# Mini_PIC18F-USB_Trainer_SCH.net
KiCad netlist of a schematic drawn in EAGLE
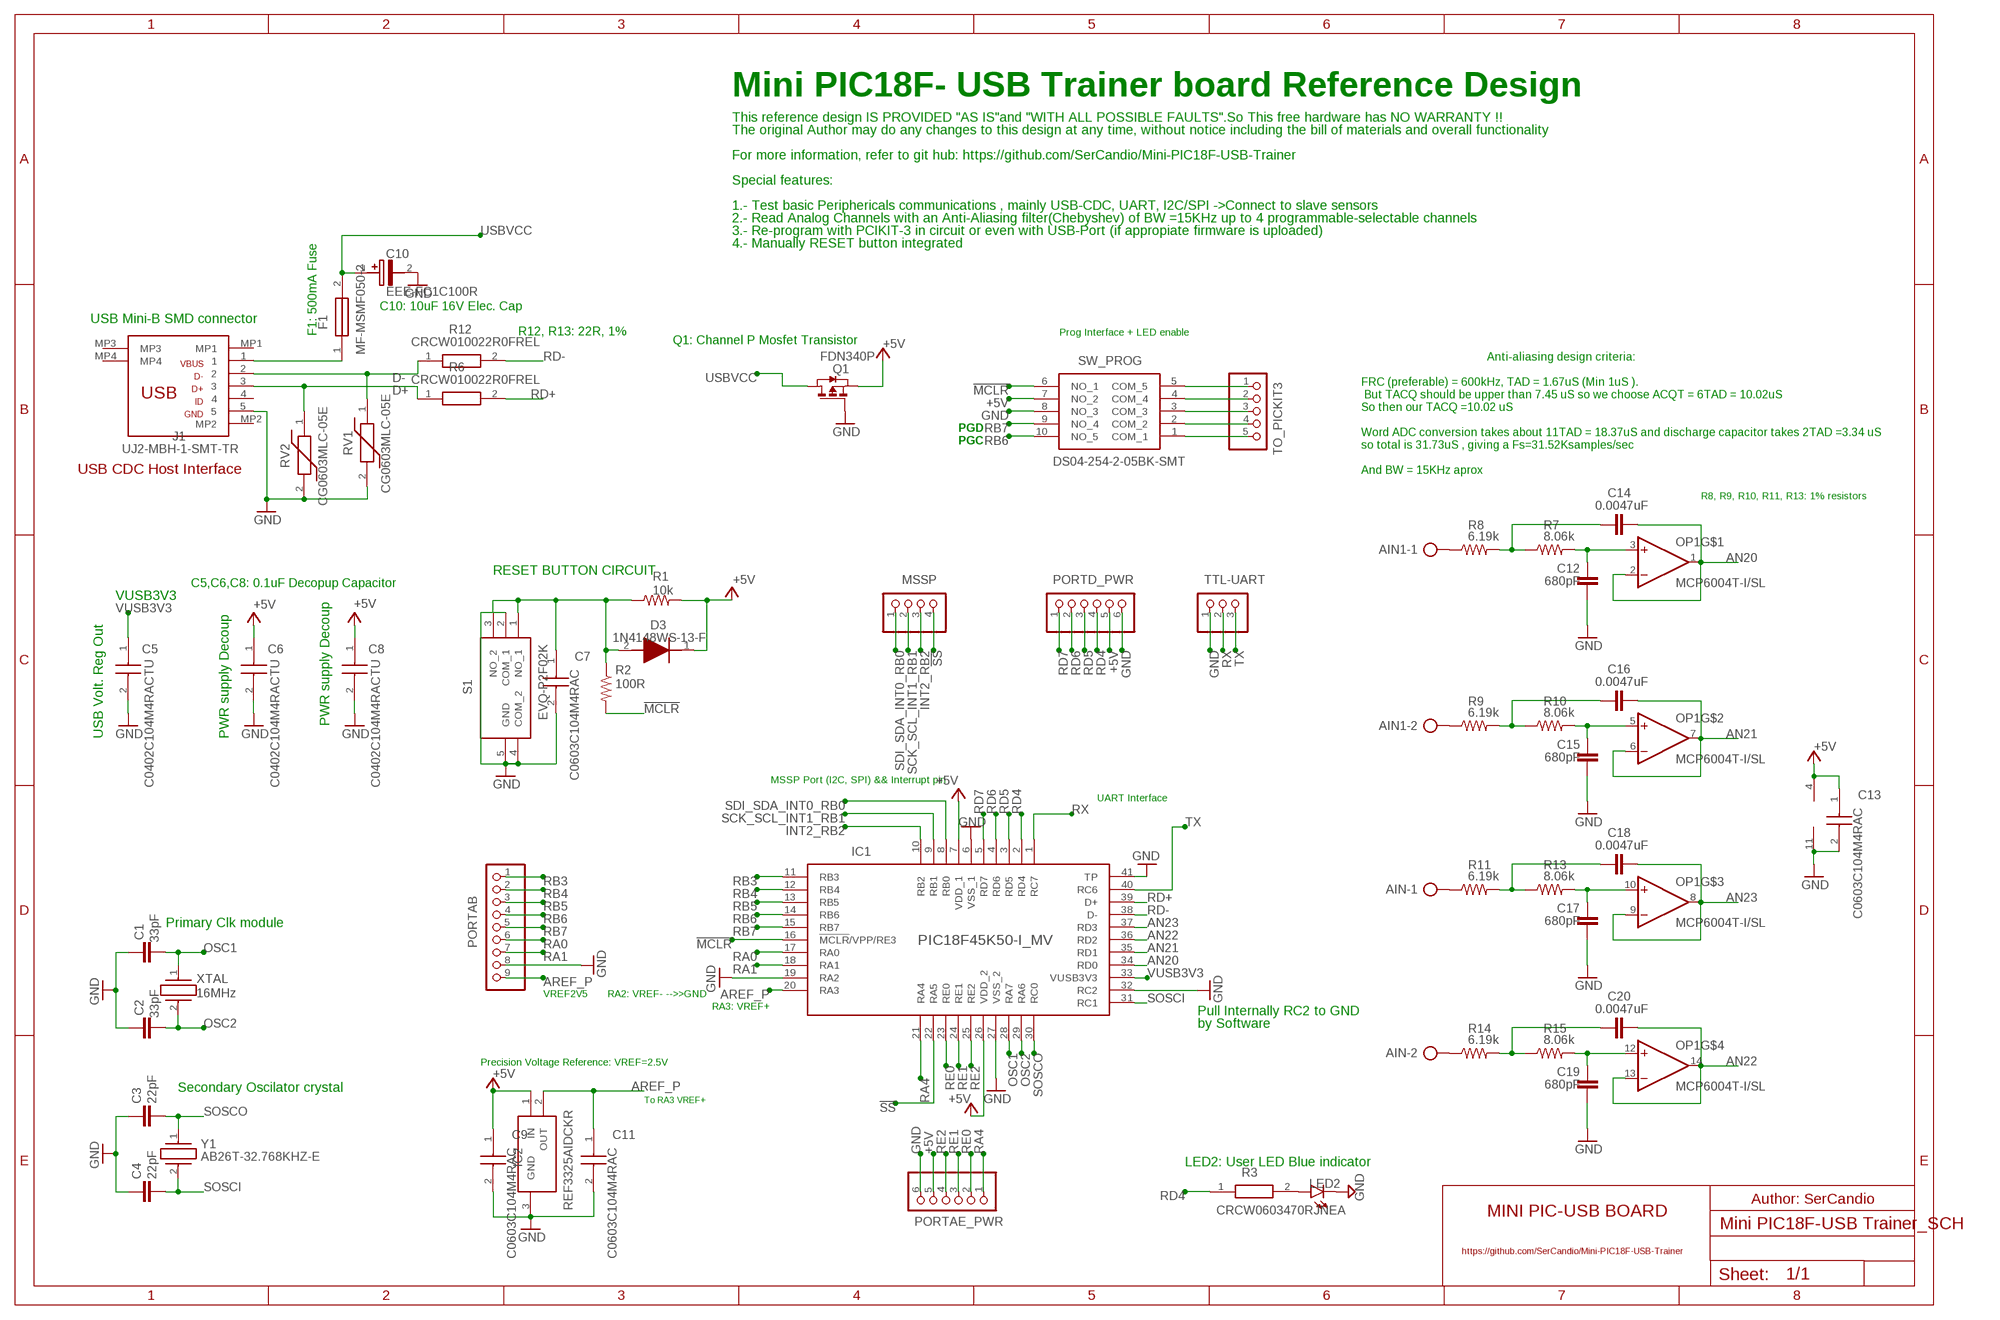
[diagram p0: schematic, sheet 1]

(export (version "E")
  (design (tool "Eeschema 10.0.6"))
  (components
    (comp (ref "AIN")
      (value "AK500/2-H")
      (footprint "eagle-import:AK500_2-H")
      (fields (field (name "LCSC_PART_NUMBER") "C91153") (field (name "MANUFACTURER_PART_NUMBER") "1729128"))
      (libsource (lib "eagle-import") (part "AK500/2-H"))
    )
    (comp (ref "AIN1")
      (value "AK500/2-H")
      (footprint "eagle-import:AK500_2-H")
      (fields (field (name "LCSC_PART_NUMBER") "C91153") (field (name "MANUFACTURER_PART_NUMBER") "1729128"))
      (libsource (lib "eagle-import") (part "AK500/2-H"))
    )
    (comp (ref "C1")
      (value "33pF")
      (footprint "eagle-import:C0603K")
      (description "Capacitores cerámicos de capas múltiples (MLCC) - SMD/SMT WCAP-CSGP 33pF 0603 5% 16V MLCC")
      (fields
        (field (name "MANUFACTURER_PART_NUMBER") "885012006020")
        (field (name "MOUSER_PART_NUMBER") "710-885012006020")
      )
      (libsource (lib "eagle-import") (part "C-EUC0603K"))
    )
    (comp (ref "C2")
      (value "33pF")
      (footprint "eagle-import:C0603K")
      (description "Capacitores cerámicos de capas múltiples (MLCC) - SMD/SMT WCAP-CSGP 33pF 0603 5% 16V MLCC")
      (fields
        (field (name "MANUFACTURER_PART_NUMBER") "885012006020")
        (field (name "MOUSER_PART_NUMBER") "710-885012006020")
      )
      (libsource (lib "eagle-import") (part "C-EUC0603K"))
    )
    (comp (ref "C3")
      (value "22pF")
      (footprint "eagle-import:C0603K")
      (description "Capacitores cerámicos de capas múltiples (MLCC) - SMD/SMT 16V 22pF C0G 0603 5%")
      (fields
        (field (name "MANUFACTURER_PART_NUMBER") "0603YA220JAT2A")
        (field (name "MOUSER_PART_NUMBER") "581-0603YA220JAT2A")
      )
      (libsource (lib "eagle-import") (part "C-EUC0603K"))
    )
    (comp (ref "C4")
      (value "22pF")
      (footprint "eagle-import:C0603K")
      (description "Capacitores cerámicos de capas múltiples (MLCC) - SMD/SMT 16V 22pF C0G 0603 5%")
      (fields
        (field (name "MANUFACTURER_PART_NUMBER") "0603YA220JAT2A")
        (field (name "MOUSER_PART_NUMBER") "581-0603YA220JAT2A")
      )
      (libsource (lib "eagle-import") (part "C-EUC0603K"))
    )
    (comp (ref "C5")
      (value "C0402C104M4RACTU")
      (footprint "eagle-import:C0402C104J4RACTU")
      (fields (field (name "MOUSER_PART_NUMBER") "80-C0402C104M4R"))
      (libsource (lib "eagle-import") (part "C0402C104M4RACTU"))
    )
    (comp (ref "C6")
      (value "C0402C104M4RACTU")
      (footprint "eagle-import:C0402C104J4RACTU")
      (fields (field (name "MOUSER_PART_NUMBER") "80-C0402C104M4R"))
      (libsource (lib "eagle-import") (part "C0402C104M4RACTU"))
    )
    (comp (ref "C7")
      (value "C0603C104M4RAC")
      (footprint "eagle-import:CAPC1608X95N")
      (fields (field (name "MOUSER_PART_NUMBER") "80-C0603C104M4RAC"))
      (libsource (lib "eagle-import") (part "C0603C104M4RAC"))
    )
    (comp (ref "C8")
      (value "C0402C104M4RACTU")
      (footprint "eagle-import:C0402C104J4RACTU")
      (fields (field (name "MOUSER_PART_NUMBER") "80-C0402C104M4R"))
      (libsource (lib "eagle-import") (part "C0402C104M4RACTU"))
    )
    (comp (ref "C9")
      (value "C0603C104M4RAC")
      (footprint "eagle-import:CAPC1608X95N")
      (fields (field (name "MOUSER_PART_NUMBER") "80-C0603C104M4RAC"))
      (libsource (lib "eagle-import") (part "C0603C104M4RAC"))
    )
    (comp (ref "C10")
      (value "EEE-FC1C100R")
      (footprint "eagle-import:EEE1AA220WR")
      (fields (field (name "MOUSER_PART_NUMBER") "667-EEE-FC1C100R"))
      (libsource (lib "eagle-import") (part "EEE-FC1C100R"))
    )
    (comp (ref "C11")
      (value "C0603C104M4RAC")
      (footprint "eagle-import:CAPC1608X95N")
      (fields (field (name "MOUSER_PART_NUMBER") "80-C0603C104M4RAC"))
      (libsource (lib "eagle-import") (part "C0603C104M4RAC"))
    )
    (comp (ref "C12")
      (value "680pF")
      (footprint "eagle-import:C0603K")
      (description "Capacitores cerámicos de capas múltiples (MLCC) - SMD/SMT WCAP-CSGP 680pF 0603 5% 16V MLCC")
      (fields
        (field (name "MANUFACTURER_PART_NUMBER") "885012006028")
        (field (name "MOUSER_PART_NUMBER") "710-885012006028")
      )
      (libsource (lib "eagle-import") (part "C-EUC0603K"))
    )
    (comp (ref "C13")
      (value "C0603C104M4RAC")
      (footprint "eagle-import:CAPC1608X95N")
      (fields (field (name "MOUSER_PART_NUMBER") "80-C0603C104M4RAC"))
      (libsource (lib "eagle-import") (part "C0603C104M4RAC"))
    )
    (comp (ref "C14")
      (value "0.0047uF")
      (footprint "eagle-import:C0603K")
      (description "Capacitores cerámicos de capas múltiples (MLCC) - SMD/SMT 0603 4700pF 16volts X7R 5%")
      (fields
        (field (name "MANUFACTURER_PART_NUMBER") "VJ0603Y472JXJCW1BC")
        (field (name "MOUSER_PART_NUMBER") "77-VJ0603Y472JXJCBC")
      )
      (libsource (lib "eagle-import") (part "C-EUC0603K"))
    )
    (comp (ref "C15")
      (value "680pF")
      (footprint "eagle-import:C0603K")
      (description "Capacitores cerámicos de capas múltiples (MLCC) - SMD/SMT WCAP-CSGP 680pF 0603 5% 16V MLCC")
      (fields
        (field (name "MANUFACTURER_PART_NUMBER") "885012006028")
        (field (name "MOUSER_PART_NUMBER") "710-885012006028")
      )
      (libsource (lib "eagle-import") (part "C-EUC0603K"))
    )
    (comp (ref "C16")
      (value "0.0047uF")
      (footprint "eagle-import:C0603K")
      (description "Capacitores cerámicos de capas múltiples (MLCC) - SMD/SMT 0603 4700pF 16volts X7R 5%")
      (fields
        (field (name "MANUFACTURER_PART_NUMBER") "VJ0603Y472JXJCW1BC")
        (field (name "MOUSER_PART_NUMBER") "77-VJ0603Y472JXJCBC")
      )
      (libsource (lib "eagle-import") (part "C-EUC0603K"))
    )
    (comp (ref "C17")
      (value "680pF")
      (footprint "eagle-import:C0603K")
      (description "Capacitores cerámicos de capas múltiples (MLCC) - SMD/SMT WCAP-CSGP 680pF 0603 5% 16V MLCC")
      (fields
        (field (name "MANUFACTURER_PART_NUMBER") "885012006028")
        (field (name "MOUSER_PART_NUMBER") "710-885012006028")
      )
      (libsource (lib "eagle-import") (part "C-EUC0603K"))
    )
    (comp (ref "C18")
      (value "0.0047uF")
      (footprint "eagle-import:C0603K")
      (description "Capacitores cerámicos de capas múltiples (MLCC) - SMD/SMT 0603 4700pF 16volts X7R 5%")
      (fields
        (field (name "MANUFACTURER_PART_NUMBER") "VJ0603Y472JXJCW1BC")
        (field (name "MOUSER_PART_NUMBER") "77-VJ0603Y472JXJCBC")
      )
      (libsource (lib "eagle-import") (part "C-EUC0603K"))
    )
    (comp (ref "C19")
      (value "680pF")
      (footprint "eagle-import:C0603K")
      (description "Capacitores cerámicos de capas múltiples (MLCC) - SMD/SMT WCAP-CSGP 680pF 0603 5% 16V MLCC")
      (fields
        (field (name "MANUFACTURER_PART_NUMBER") "885012006028")
        (field (name "MOUSER_PART_NUMBER") "710-885012006028")
      )
      (libsource (lib "eagle-import") (part "C-EUC0603K"))
    )
    (comp (ref "C20")
      (value "0.0047uF")
      (footprint "eagle-import:C0603K")
      (description "Capacitores cerámicos de capas múltiples (MLCC) - SMD/SMT 0603 4700pF 16volts X7R 5%")
      (fields
        (field (name "MANUFACTURER_PART_NUMBER") "VJ0603Y472JXJCW1BC")
        (field (name "MOUSER_PART_NUMBER") "77-VJ0603Y472JXJCBC")
      )
      (libsource (lib "eagle-import") (part "C-EUC0603K"))
    )
    (comp (ref "D3")
      (value "1N4148WS-13-F")
      (footprint "eagle-import:SOD2513X120N")
      (fields (field (name "MOUSER_PART_NUMBER") "621-1N4148WS-13-F"))
      (libsource (lib "eagle-import") (part "1N4148WS-13-F"))
    )
    (comp (ref "F1")
      (value "MF-MSMF050-2")
      (footprint "eagle-import:FUSC4632X85N")
      (fields (field (name "MOUSER_PART_NUMBER") "652-MF-MSMF050-2"))
      (libsource (lib "eagle-import") (part "MF-MSMF050-2"))
    )
    (comp (ref "IC1")
      (value "PIC18F45K50-I_MV")
      (footprint "eagle-import:QFN40P500X500X55-41N")
      (fields
        (field (name "MANUFACTURER_PART_NUMBER") "PIC18F45K50-I/MV")
        (field (name "MOUSER_PART_NUMBER") "579-PIC18F45K50-I/MV")
      )
      (libsource (lib "eagle-import") (part "PIC18F45K50-I_MV"))
    )
    (comp (ref "IC2")
      (value "REF3325AIDCKR")
      (footprint "eagle-import:SOT65P210X110-3N")
      (fields (field (name "MOUSER_PART_NUMBER") "595-REF3325AIDCKR"))
      (libsource (lib "eagle-import") (part "REF3325AIDCKR"))
    )
    (comp (ref "J1")
      (value "UJ2-MBH-1-SMT-TR")
      (footprint "eagle-import:UJ2MBH1SMTTR")
      (fields (field (name "MOUSER_PART_NUMBER") "490-UJ2-MBH-1-SMT"))
      (libsource (lib "eagle-import") (part "UJ2-MBH-1-SMT-TR"))
    )
    (comp (ref "LED2")
      (value "LEDCHIP-LED0805")
      (footprint "eagle-import:CHIP-LED0805")
      (description "LED estándar - SMD (montaje superficial) WL-SMCW SMDMono TpVw Waterclr 0805 Blue")
      (fields
        (field (name "MANUFACTURER_PART_NUMBER") "150080BS75000")
        (field (name "MOUSER_PART_NUMBER") "710-150080BS75000")
      )
      (libsource (lib "eagle-import") (part "LEDCHIP-LED0805"))
    )
    (comp (ref "MSSP")
      (value "PINHD-1X4")
      (footprint "eagle-import:1X04")
      (libsource (lib "eagle-import") (part "PINHD-1X4"))
    )
    (comp (ref "OP1")
      (value "MCP6004T-I/SL")
      (footprint "eagle-import:SOIC127P600X175-14M")
      (fields
        (field (name "LCSC_PART_NUMBER") "C7378")
        (field (name "MANUFACTURER_PART_NUMBER") " MCP6004T-I/SL")
        (field (name "MOUSER_PART_NUMBER") "579-MCP6004T-I/SL")
      )
      (libsource (lib "eagle-import") (part "MCP6004T-I/SL"))
    )
    (comp (ref "PORTAB")
      (value "PINHD-1X9")
      (footprint "eagle-import:1X09")
      (libsource (lib "eagle-import") (part "PINHD-1X9"))
    )
    (comp (ref "PORTAE_PWR")
      (value "PINHD-1X6")
      (footprint "eagle-import:1X06")
      (libsource (lib "eagle-import") (part "PINHD-1X6"))
    )
    (comp (ref "PORTD_PWR")
      (value "PINHD-1X6")
      (footprint "eagle-import:1X06")
      (libsource (lib "eagle-import") (part "PINHD-1X6"))
    )
    (comp (ref "Q1")
      (value "FDN340P")
      (footprint "eagle-import:SOT95P237X112-3N")
      (fields (field (name "MOUSER_PART_NUMBER") "512-FDN340P"))
      (libsource (lib "eagle-import") (part "FDN340P"))
    )
    (comp (ref "R1")
      (value "10k")
      (footprint "eagle-import:R0402")
      (description "Resistores de película gruesa - SMD 10K OHM 5%")
      (fields
        (field (name "MANUFACTURER_PART_NUMBER") "CR0402-JW-103GLF")
        (field (name "MOUSER_PART_NUMBER") "652-CR0402-JW-103GLF")
      )
      (libsource (lib "eagle-import") (part "R-US_R0402"))
    )
    (comp (ref "R2")
      (value "100R")
      (footprint "eagle-import:R0402")
      (description "Resistores de película gruesa - SMD 100 OHM 5%")
      (fields
        (field (name "MANUFACTURER_PART_NUMBER") "CR0402-JW-101GLF")
        (field (name "MOUSER_PART_NUMBER") "652-CR0402JW-101GLF")
      )
      (libsource (lib "eagle-import") (part "R-US_R0402"))
    )
    (comp (ref "R3")
      (value "CRCW0603470RJNEA")
      (footprint "eagle-import:RESC1608X50N")
      (fields (field (name "MOUSER_PART_NUMBER") "71-CRCW0603J-470-E3"))
      (libsource (lib "eagle-import") (part "CRCW0603470RJNEA"))
    )
    (comp (ref "R6")
      (value "CRCW010022R0FREL")
      (footprint "eagle-import:RESC0402X15N")
      (fields (field (name "MOUSER_PART_NUMBER") "71-CRCW010022R0FREL"))
      (libsource (lib "eagle-import") (part "CRCW010022R0FREL"))
    )
    (comp (ref "R7")
      (value "8.06k")
      (footprint "eagle-import:R0603")
      (description "Resistores de película gruesa - SMD 8.06K ohm 1%")
      (fields
        (field (name "MANUFACTURER_PART_NUMBER") "CR0603-FX-8061ELF")
        (field (name "MOUSER_PART_NUMBER") "652-CR0603FX-8061ELF")
      )
      (libsource (lib "eagle-import") (part "R-US_R0603"))
    )
    (comp (ref "R8")
      (value "6.19k")
      (footprint "eagle-import:R0603")
      (description "Resistores de película gruesa - SMD 6.19K ohm 1%")
      (fields
        (field (name "MANUFACTURER_PART_NUMBER") "CR0603-FX-6191ELF")
        (field (name "MOUSER_PART_NUMBER") "652-CR0603FX-6191ELF")
      )
      (libsource (lib "eagle-import") (part "R-US_R0603"))
    )
    (comp (ref "R9")
      (value "6.19k")
      (footprint "eagle-import:R0603")
      (description "Resistores de película gruesa - SMD 6.19K ohm 1%")
      (fields
        (field (name "MANUFACTURER_PART_NUMBER") "CR0603-FX-6191ELF")
        (field (name "MOUSER_PART_NUMBER") "652-CR0603FX-6191ELF")
      )
      (libsource (lib "eagle-import") (part "R-US_R0603"))
    )
    (comp (ref "R10")
      (value "8.06k")
      (footprint "eagle-import:R0603")
      (description "Resistores de película gruesa - SMD 8.06K ohm 1%")
      (fields
        (field (name "MANUFACTURER_PART_NUMBER") "CR0603-FX-8061ELF")
        (field (name "MOUSER_PART_NUMBER") "652-CR0603FX-8061ELF")
      )
      (libsource (lib "eagle-import") (part "R-US_R0603"))
    )
    (comp (ref "R11")
      (value "6.19k")
      (footprint "eagle-import:R0603")
      (description "Resistores de película gruesa - SMD 6.19K ohm 1%")
      (fields
        (field (name "MANUFACTURER_PART_NUMBER") "CR0603-FX-6191ELF")
        (field (name "MOUSER_PART_NUMBER") "652-CR0603FX-6191ELF")
      )
      (libsource (lib "eagle-import") (part "R-US_R0603"))
    )
    (comp (ref "R12")
      (value "CRCW010022R0FREL")
      (footprint "eagle-import:RESC0402X15N")
      (fields (field (name "MOUSER_PART_NUMBER") "71-CRCW010022R0FREL"))
      (libsource (lib "eagle-import") (part "CRCW010022R0FREL"))
    )
    (comp (ref "R13")
      (value "8.06k")
      (footprint "eagle-import:R0603")
      (description "Resistores de película gruesa - SMD 8.06K ohm 1%")
      (fields
        (field (name "MANUFACTURER_PART_NUMBER") "CR0603-FX-8061ELF")
        (field (name "MOUSER_PART_NUMBER") "652-CR0603FX-8061ELF")
      )
      (libsource (lib "eagle-import") (part "R-US_R0603"))
    )
    (comp (ref "R14")
      (value "6.19k")
      (footprint "eagle-import:R0603")
      (description "Resistores de película gruesa - SMD 6.19K ohm 1%")
      (fields
        (field (name "MANUFACTURER_PART_NUMBER") "CR0603-FX-6191ELF")
        (field (name "MOUSER_PART_NUMBER") "652-CR0603FX-6191ELF")
      )
      (libsource (lib "eagle-import") (part "R-US_R0603"))
    )
    (comp (ref "R15")
      (value "8.06k")
      (footprint "eagle-import:R0603")
      (description "Resistores de película gruesa - SMD 8.06K ohm 1%")
      (fields
        (field (name "MANUFACTURER_PART_NUMBER") "CR0603-FX-8061ELF")
        (field (name "MOUSER_PART_NUMBER") "652-CR0603FX-8061ELF")
      )
      (libsource (lib "eagle-import") (part "R-US_R0603"))
    )
    (comp (ref "RV1")
      (value "CG0603MLC-05E")
      (footprint "eagle-import:VARC1608X55N")
      (fields (field (name "MOUSER_PART_NUMBER") "652-CG0603MLC-05E"))
      (libsource (lib "eagle-import") (part "CG0603MLC-05E"))
    )
    (comp (ref "RV2")
      (value "CG0603MLC-05E")
      (footprint "eagle-import:VARC1608X55N")
      (fields (field (name "MOUSER_PART_NUMBER") "652-CG0603MLC-05E"))
      (libsource (lib "eagle-import") (part "CG0603MLC-05E"))
    )
    (comp (ref "S1")
      (value "EVQ-P2F02K")
      (footprint "eagle-import:EVQP2V02W")
      (fields (field (name "MOUSER_PART_NUMBER") "667-EVQ-P2F02K"))
      (libsource (lib "eagle-import") (part "EVQ-P2F02K"))
    )
    (comp (ref "SW_PROG")
      (value "DS04-254-2-05BK-SMT")
      (footprint "eagle-import:DS04254205BKSMT")
      (fields (field (name "MOUSER_PART_NUMBER") "490-DS04254205BK-SMT"))
      (libsource (lib "eagle-import") (part "DS04-254-2-05BK-SMT"))
    )
    (comp (ref "TO_PICKIT3")
      (value "PINHD-1X5/90")
      (footprint "eagle-import:1X05_90")
      (libsource (lib "eagle-import") (part "PINHD-1X5/90"))
    )
    (comp (ref "TTL-UART")
      (value "PINHD-1X3/90")
      (footprint "eagle-import:1X03_90")
      (libsource (lib "eagle-import") (part "PINHD-1X3/90"))
    )
    (comp (ref "XTAL")
      (value "16MHz")
      (footprint "eagle-import:LFXTAL020423CUTT")
      (fields
        (field (name "MANUFACTURER_PART_NUMBER") "LFXTAL003237REEL")
        (field (name "MOUSER_PART_NUMBER") "449-LFXTAL003237REEL")
      )
      (libsource (lib "eagle-import") (part "LFXTAL003237REEL"))
    )
    (comp (ref "Y1")
      (value "AB26T-32.768KHZ-E")
      (footprint "eagle-import:AB26T32768KHZE")
      (fields (field (name "MOUSER_PART_NUMBER") "815-AB26T32.768KHZE"))
      (libsource (lib "eagle-import") (part "AB26T-32.768KHZ-E"))
    )
  )
  (nets
    (net (code "1") (name "+5V") (class "Default")
      (node (ref "C13") (pin "1") (pinfunction "1_1") (pintype "bidirectional"))
      (node (ref "C6") (pin "1") (pinfunction "1_1") (pintype "bidirectional"))
      (node (ref "C8") (pin "1") (pinfunction "1_1") (pintype "bidirectional"))
      (node (ref "C9") (pin "1") (pinfunction "1_1") (pintype "bidirectional"))
      (node (ref "D3") (pin "1") (pinfunction "K_1") (pintype "bidirectional"))
      (node (ref "IC1") (pin "26") (pinfunction "VDD_2_26") (pintype "bidirectional"))
      (node (ref "IC1") (pin "7") (pinfunction "VDD_1_7") (pintype "bidirectional"))
      (node (ref "IC2") (pin "1") (pinfunction "IN_1") (pintype "bidirectional"))
      (node (ref "OP1") (pin "4") (pinfunction "V+_4") (pintype "power_in"))
      (node (ref "PORTAE_PWR") (pin "5") (pinfunction "5_5") (pintype "passive"))
      (node (ref "PORTD_PWR") (pin "5") (pinfunction "5_5") (pintype "passive"))
      (node (ref "Q1") (pin "2") (pinfunction "S_2") (pintype "passive"))
      (node (ref "R1") (pin "2") (pinfunction "2_2") (pintype "passive"))
      (node (ref "SW_PROG") (pin "7") (pinfunction "NO_2_7") (pintype "bidirectional"))
    )
    (net (code "2") (name "/AN20") (class "Default")
      (node (ref "C14") (pin "2") (pinfunction "2_2") (pintype "passive"))
      (node (ref "IC1") (pin "34") (pinfunction "RD0_34") (pintype "bidirectional"))
      (node (ref "OP1") (pin "1") (pinfunction "OUT_1") (pintype "output"))
      (node (ref "OP1") (pin "2") (pinfunction "-IN_2") (pintype "input"))
    )
    (net (code "3") (name "/AN21") (class "Default")
      (node (ref "C16") (pin "2") (pinfunction "2_2") (pintype "passive"))
      (node (ref "IC1") (pin "35") (pinfunction "RD1_35") (pintype "bidirectional"))
      (node (ref "OP1") (pin "6") (pinfunction "-IN_6") (pintype "input"))
      (node (ref "OP1") (pin "7") (pinfunction "OUT_7") (pintype "output"))
    )
    (net (code "4") (name "/AN22") (class "Default")
      (node (ref "C20") (pin "2") (pinfunction "2_2") (pintype "passive"))
      (node (ref "IC1") (pin "36") (pinfunction "RD2_36") (pintype "bidirectional"))
      (node (ref "OP1") (pin "13") (pinfunction "-IN_13") (pintype "input"))
      (node (ref "OP1") (pin "14") (pinfunction "OUT_14") (pintype "output"))
    )
    (net (code "5") (name "/AN23") (class "Default")
      (node (ref "C18") (pin "2") (pinfunction "2_2") (pintype "passive"))
      (node (ref "IC1") (pin "37") (pinfunction "RD3_37") (pintype "bidirectional"))
      (node (ref "OP1") (pin "8") (pinfunction "OUT_8") (pintype "output"))
      (node (ref "OP1") (pin "9") (pinfunction "-IN_9") (pintype "input"))
    )
    (net (code "6") (name "/AREF_P") (class "Default")
      (node (ref "C11") (pin "1") (pinfunction "1_1") (pintype "bidirectional"))
      (node (ref "IC1") (pin "20") (pinfunction "RA3_20") (pintype "bidirectional"))
      (node (ref "IC2") (pin "2") (pinfunction "OUT_2") (pintype "bidirectional"))
      (node (ref "PORTAB") (pin "9") (pinfunction "9_9") (pintype "passive"))
    )
    (net (code "7") (name "/D+") (class "Default")
      (node (ref "J1") (pin "3") (pinfunction "3_3") (pintype "bidirectional"))
      (node (ref "R6") (pin "1") (pinfunction "1_1") (pintype "bidirectional"))
      (node (ref "RV2") (pin "1") (pinfunction "1_1") (pintype "bidirectional"))
    )
    (net (code "8") (name "/D-") (class "Default")
      (node (ref "J1") (pin "2") (pinfunction "2_2") (pintype "bidirectional"))
      (node (ref "R12") (pin "1") (pinfunction "1_1") (pintype "bidirectional"))
      (node (ref "RV1") (pin "1") (pinfunction "1_1") (pintype "bidirectional"))
    )
    (net (code "9") (name "/INT2_RB2") (class "Default")
      (node (ref "IC1") (pin "10") (pinfunction "RB2_10") (pintype "bidirectional"))
      (node (ref "MSSP") (pin "3") (pinfunction "3_3") (pintype "passive"))
    )
    (net (code "10") (name "/OSC1") (class "Default")
      (node (ref "C1") (pin "2") (pinfunction "2_2") (pintype "passive"))
      (node (ref "IC1") (pin "28") (pinfunction "RA7_28") (pintype "bidirectional"))
      (node (ref "XTAL") (pin "1") (pinfunction "1_1") (pintype "bidirectional"))
    )
    (net (code "11") (name "/OSC2") (class "Default")
      (node (ref "C2") (pin "2") (pinfunction "2_2") (pintype "passive"))
      (node (ref "IC1") (pin "29") (pinfunction "RA6_29") (pintype "bidirectional"))
      (node (ref "XTAL") (pin "2") (pinfunction "2_2") (pintype "bidirectional"))
    )
    (net (code "12") (name "/RA0") (class "Default")
      (node (ref "IC1") (pin "17") (pinfunction "RA0_17") (pintype "bidirectional"))
      (node (ref "PORTAB") (pin "6") (pinfunction "6_6") (pintype "passive"))
    )
    (net (code "13") (name "/RA1") (class "Default")
      (node (ref "IC1") (pin "18") (pinfunction "RA1_18") (pintype "bidirectional"))
      (node (ref "PORTAB") (pin "7") (pinfunction "7_7") (pintype "passive"))
    )
    (net (code "14") (name "/RA4") (class "Default")
      (node (ref "IC1") (pin "21") (pinfunction "RA4_21") (pintype "bidirectional"))
      (node (ref "PORTAE_PWR") (pin "1") (pinfunction "1_1") (pintype "passive"))
    )
    (net (code "15") (name "/RB3") (class "Default")
      (node (ref "IC1") (pin "11") (pinfunction "RB3_11") (pintype "bidirectional"))
      (node (ref "PORTAB") (pin "1") (pinfunction "1_1") (pintype "passive"))
    )
    (net (code "16") (name "/RB4") (class "Default")
      (node (ref "IC1") (pin "12") (pinfunction "RB4_12") (pintype "bidirectional"))
      (node (ref "PORTAB") (pin "2") (pinfunction "2_2") (pintype "passive"))
    )
    (net (code "17") (name "/RB5") (class "Default")
      (node (ref "IC1") (pin "13") (pinfunction "RB5_13") (pintype "bidirectional"))
      (node (ref "PORTAB") (pin "3") (pinfunction "3_3") (pintype "passive"))
    )
    (net (code "18") (name "/RB6") (class "Default")
      (node (ref "IC1") (pin "14") (pinfunction "RB6_14") (pintype "bidirectional"))
      (node (ref "PORTAB") (pin "4") (pinfunction "4_4") (pintype "passive"))
      (node (ref "SW_PROG") (pin "10") (pinfunction "NO_5_10") (pintype "bidirectional"))
    )
    (net (code "19") (name "/RB7") (class "Default")
      (node (ref "IC1") (pin "15") (pinfunction "RB7_15") (pintype "bidirectional"))
      (node (ref "PORTAB") (pin "5") (pinfunction "5_5") (pintype "passive"))
      (node (ref "SW_PROG") (pin "9") (pinfunction "NO_4_9") (pintype "bidirectional"))
    )
    (net (code "20") (name "/RD+") (class "Default")
      (node (ref "IC1") (pin "39") (pinfunction "D+_39") (pintype "bidirectional"))
      (node (ref "R6") (pin "2") (pinfunction "2_2") (pintype "bidirectional"))
    )
    (net (code "21") (name "/RD-") (class "Default")
      (node (ref "IC1") (pin "38") (pinfunction "D-_38") (pintype "bidirectional"))
      (node (ref "R12") (pin "2") (pinfunction "2_2") (pintype "bidirectional"))
    )
    (net (code "22") (name "/RD4") (class "Default")
      (node (ref "IC1") (pin "2") (pinfunction "RD4_2") (pintype "bidirectional"))
      (node (ref "PORTD_PWR") (pin "4") (pinfunction "4_4") (pintype "passive"))
      (node (ref "R3") (pin "1") (pinfunction "1_1") (pintype "bidirectional"))
    )
    (net (code "23") (name "/RD5") (class "Default")
      (node (ref "IC1") (pin "3") (pinfunction "RD5_3") (pintype "bidirectional"))
      (node (ref "PORTD_PWR") (pin "3") (pinfunction "3_3") (pintype "passive"))
    )
    (net (code "24") (name "/RD6") (class "Default")
      (node (ref "IC1") (pin "4") (pinfunction "RD6_4") (pintype "bidirectional"))
      (node (ref "PORTD_PWR") (pin "2") (pinfunction "2_2") (pintype "passive"))
    )
    (net (code "25") (name "/RD7") (class "Default")
      (node (ref "IC1") (pin "5") (pinfunction "RD7_5") (pintype "bidirectional"))
      (node (ref "PORTD_PWR") (pin "1") (pinfunction "1_1") (pintype "passive"))
    )
    (net (code "26") (name "/RE0") (class "Default")
      (node (ref "IC1") (pin "23") (pinfunction "RE0_23") (pintype "bidirectional"))
      (node (ref "PORTAE_PWR") (pin "2") (pinfunction "2_2") (pintype "passive"))
    )
    (net (code "27") (name "/RE1") (class "Default")
      (node (ref "IC1") (pin "24") (pinfunction "RE1_24") (pintype "bidirectional"))
      (node (ref "PORTAE_PWR") (pin "3") (pinfunction "3_3") (pintype "passive"))
    )
    (net (code "28") (name "/RE2") (class "Default")
      (node (ref "IC1") (pin "25") (pinfunction "RE2_25") (pintype "bidirectional"))
      (node (ref "PORTAE_PWR") (pin "4") (pinfunction "4_4") (pintype "passive"))
    )
    (net (code "29") (name "/RX") (class "Default")
      (node (ref "IC1") (pin "1") (pinfunction "RC7_1") (pintype "bidirectional"))
      (node (ref "TTL-UART") (pin "2") (pinfunction "2_2") (pintype "passive"))
    )
    (net (code "30") (name "/SCK_SCL_INT1_RB1") (class "Default")
      (node (ref "IC1") (pin "9") (pinfunction "RB1_9") (pintype "bidirectional"))
      (node (ref "MSSP") (pin "2") (pinfunction "2_2") (pintype "passive"))
    )
    (net (code "31") (name "/SDI_SDA_INT0_RB0") (class "Default")
      (node (ref "IC1") (pin "8") (pinfunction "RB0_8") (pintype "bidirectional"))
      (node (ref "MSSP") (pin "1") (pinfunction "1_1") (pintype "passive"))
    )
    (net (code "32") (name "/SOSCI") (class "Default")
      (node (ref "C4") (pin "2") (pinfunction "2_2") (pintype "passive"))
      (node (ref "IC1") (pin "31") (pinfunction "RC1_31") (pintype "bidirectional"))
      (node (ref "Y1") (pin "2") (pinfunction "2_2") (pintype "bidirectional"))
    )
    (net (code "33") (name "/SOSCO") (class "Default")
      (node (ref "C3") (pin "2") (pinfunction "2_2") (pintype "passive"))
      (node (ref "IC1") (pin "30") (pinfunction "RC0_30") (pintype "bidirectional"))
      (node (ref "Y1") (pin "1") (pinfunction "1_1") (pintype "bidirectional"))
    )
    (net (code "34") (name "/TX") (class "Default")
      (node (ref "IC1") (pin "40") (pinfunction "RC6_40") (pintype "bidirectional"))
      (node (ref "TTL-UART") (pin "3") (pinfunction "3_3") (pintype "passive"))
    )
    (net (code "35") (name "/USBVCC") (class "Default")
      (node (ref "C10") (pin "1") (pinfunction "+_1") (pintype "bidirectional"))
      (node (ref "F1") (pin "2") (pinfunction "2_2") (pintype "bidirectional"))
      (node (ref "Q1") (pin "3") (pinfunction "D_3") (pintype "passive"))
    )
    (net (code "36") (name "/VUSB3V3") (class "Default")
      (node (ref "C5") (pin "1") (pinfunction "1_1") (pintype "bidirectional"))
      (node (ref "IC1") (pin "33") (pinfunction "VUSB3V3_33") (pintype "bidirectional"))
    )
    (net (code "37") (name "/~{MCLR}") (class "Default")
      (node (ref "IC1") (pin "16") (pinfunction "~{MCLR}/VPP/RE3_16") (pintype "bidirectional"))
      (node (ref "R2") (pin "2") (pinfunction "2_2") (pintype "passive"))
      (node (ref "SW_PROG") (pin "6") (pinfunction "NO_1_6") (pintype "bidirectional"))
    )
    (net (code "38") (name "/~{SS}") (class "Default")
      (node (ref "IC1") (pin "22") (pinfunction "RA5_22") (pintype "bidirectional"))
      (node (ref "MSSP") (pin "4") (pinfunction "4_4") (pintype "passive"))
    )
    (net (code "39") (name "GND") (class "Default")
      (node (ref "C1") (pin "1") (pinfunction "1_1") (pintype "passive"))
      (node (ref "C10") (pin "2") (pinfunction "-_2") (pintype "bidirectional"))
      (node (ref "C11") (pin "2") (pinfunction "2_2") (pintype "bidirectional"))
      (node (ref "C12") (pin "2") (pinfunction "2_2") (pintype "passive"))
      (node (ref "C13") (pin "2") (pinfunction "2_2") (pintype "bidirectional"))
      (node (ref "C15") (pin "2") (pinfunction "2_2") (pintype "passive"))
      (node (ref "C17") (pin "2") (pinfunction "2_2") (pintype "passive"))
      (node (ref "C19") (pin "2") (pinfunction "2_2") (pintype "passive"))
      (node (ref "C2") (pin "1") (pinfunction "1_1") (pintype "passive"))
      (node (ref "C3") (pin "1") (pinfunction "1_1") (pintype "passive"))
      (node (ref "C4") (pin "1") (pinfunction "1_1") (pintype "passive"))
      (node (ref "C5") (pin "2") (pinfunction "2_2") (pintype "bidirectional"))
      (node (ref "C6") (pin "2") (pinfunction "2_2") (pintype "bidirectional"))
      (node (ref "C7") (pin "2") (pinfunction "2_2") (pintype "bidirectional"))
      (node (ref "C8") (pin "2") (pinfunction "2_2") (pintype "bidirectional"))
      (node (ref "C9") (pin "2") (pinfunction "2_2") (pintype "bidirectional"))
      (node (ref "IC1") (pin "19") (pinfunction "RA2_19") (pintype "bidirectional"))
      (node (ref "IC1") (pin "27") (pinfunction "VSS_2_27") (pintype "bidirectional"))
      (node (ref "IC1") (pin "32") (pinfunction "RC2_32") (pintype "bidirectional"))
      (node (ref "IC1") (pin "41") (pinfunction "TP_41") (pintype "bidirectional"))
      (node (ref "IC1") (pin "6") (pinfunction "VSS_1_6") (pintype "bidirectional"))
      (node (ref "IC2") (pin "3") (pinfunction "GND_3") (pintype "bidirectional"))
      (node (ref "J1") (pin "5") (pinfunction "5_5") (pintype "bidirectional"))
      (node (ref "LED2") (pin "C") (pinfunction "C_C") (pintype "passive"))
      (node (ref "OP1") (pin "11") (pinfunction "V-_11") (pintype "power_in"))
      (node (ref "PORTAB") (pin "8") (pinfunction "8_8") (pintype "passive"))
      (node (ref "PORTAE_PWR") (pin "6") (pinfunction "6_6") (pintype "passive"))
      (node (ref "PORTD_PWR") (pin "6") (pinfunction "6_6") (pintype "passive"))
      (node (ref "Q1") (pin "1") (pinfunction "G_1") (pintype "passive"))
      (node (ref "RV1") (pin "2") (pinfunction "2_2") (pintype "bidirectional"))
      (node (ref "RV2") (pin "2") (pinfunction "2_2") (pintype "bidirectional"))
      (node (ref "S1") (pin "2") (pinfunction "COM_1_2") (pintype "bidirectional"))
      (node (ref "S1") (pin "4") (pinfunction "COM_2_4") (pintype "bidirectional"))
      (node (ref "S1") (pin "5") (pinfunction "GND_5") (pintype "bidirectional"))
      (node (ref "SW_PROG") (pin "8") (pinfunction "NO_3_8") (pintype "bidirectional"))
      (node (ref "TTL-UART") (pin "1") (pinfunction "1_1") (pintype "passive"))
    )
    (net (code "40") (name "Net-(AIN1A-KL)") (class "Default")
      (node (ref "AIN1") (pin "1") (pinfunction "KL_1") (pintype "passive"))
      (node (ref "R8") (pin "1") (pinfunction "1_1") (pintype "passive"))
    )
    (net (code "41") (name "Net-(AIN1B-KL)") (class "Default")
      (node (ref "AIN1") (pin "2") (pinfunction "KL_2") (pintype "passive"))
      (node (ref "R9") (pin "1") (pinfunction "1_1") (pintype "passive"))
    )
    (net (code "42") (name "Net-(AINA-KL)") (class "Default")
      (node (ref "AIN") (pin "1") (pinfunction "KL_1") (pintype "passive"))
      (node (ref "R11") (pin "1") (pinfunction "1_1") (pintype "passive"))
    )
    (net (code "43") (name "Net-(AINB-KL)") (class "Default")
      (node (ref "AIN") (pin "2") (pinfunction "KL_2") (pintype "passive"))
      (node (ref "R14") (pin "1") (pinfunction "1_1") (pintype "passive"))
    )
    (net (code "44") (name "Net-(C14-Pad1)") (class "Default")
      (node (ref "C14") (pin "1") (pinfunction "1_1") (pintype "passive"))
      (node (ref "R7") (pin "1") (pinfunction "1_1") (pintype "passive"))
      (node (ref "R8") (pin "2") (pinfunction "2_2") (pintype "passive"))
    )
    (net (code "45") (name "Net-(C16-Pad1)") (class "Default")
      (node (ref "C16") (pin "1") (pinfunction "1_1") (pintype "passive"))
      (node (ref "R10") (pin "1") (pinfunction "1_1") (pintype "passive"))
      (node (ref "R9") (pin "2") (pinfunction "2_2") (pintype "passive"))
    )
    (net (code "46") (name "Net-(C18-Pad1)") (class "Default")
      (node (ref "C18") (pin "1") (pinfunction "1_1") (pintype "passive"))
      (node (ref "R11") (pin "2") (pinfunction "2_2") (pintype "passive"))
      (node (ref "R13") (pin "1") (pinfunction "1_1") (pintype "passive"))
    )
    (net (code "47") (name "Net-(C20-Pad1)") (class "Default")
      (node (ref "C20") (pin "1") (pinfunction "1_1") (pintype "passive"))
      (node (ref "R14") (pin "2") (pinfunction "2_2") (pintype "passive"))
      (node (ref "R15") (pin "1") (pinfunction "1_1") (pintype "passive"))
    )
    (net (code "48") (name "Net-(D3-A)") (class "Default")
      (node (ref "C7") (pin "1") (pinfunction "1_1") (pintype "bidirectional"))
      (node (ref "D3") (pin "2") (pinfunction "A_2") (pintype "bidirectional"))
      (node (ref "R1") (pin "1") (pinfunction "1_1") (pintype "passive"))
      (node (ref "R2") (pin "1") (pinfunction "1_1") (pintype "passive"))
      (node (ref "S1") (pin "1") (pinfunction "NO_1_1") (pintype "bidirectional"))
      (node (ref "S1") (pin "3") (pinfunction "NO_2_3") (pintype "bidirectional"))
    )
    (net (code "49") (name "Net-(F1-Pad1)") (class "Default")
      (node (ref "F1") (pin "1") (pinfunction "1_1") (pintype "bidirectional"))
      (node (ref "J1") (pin "1") (pinfunction "1_1") (pintype "bidirectional"))
    )
    (net (code "50") (name "Net-(LED2-PadA)") (class "Default")
      (node (ref "LED2") (pin "A") (pinfunction "A_A") (pintype "passive"))
      (node (ref "R3") (pin "2") (pinfunction "2_2") (pintype "bidirectional"))
    )
    (net (code "51") (name "Net-(OP1A-+IN)") (class "Default")
      (node (ref "C12") (pin "1") (pinfunction "1_1") (pintype "passive"))
      (node (ref "OP1") (pin "3") (pinfunction "+IN_3") (pintype "input"))
      (node (ref "R7") (pin "2") (pinfunction "2_2") (pintype "passive"))
    )
    (net (code "52") (name "Net-(OP1B-+IN)") (class "Default")
      (node (ref "C15") (pin "1") (pinfunction "1_1") (pintype "passive"))
      (node (ref "OP1") (pin "5") (pinfunction "+IN_5") (pintype "input"))
      (node (ref "R10") (pin "2") (pinfunction "2_2") (pintype "passive"))
    )
    (net (code "53") (name "Net-(OP1C-+IN)") (class "Default")
      (node (ref "C17") (pin "1") (pinfunction "1_1") (pintype "passive"))
      (node (ref "OP1") (pin "10") (pinfunction "+IN_10") (pintype "input"))
      (node (ref "R13") (pin "2") (pinfunction "2_2") (pintype "passive"))
    )
    (net (code "54") (name "Net-(OP1D-+IN)") (class "Default")
      (node (ref "C19") (pin "1") (pinfunction "1_1") (pintype "passive"))
      (node (ref "OP1") (pin "12") (pinfunction "+IN_12") (pintype "input"))
      (node (ref "R15") (pin "2") (pinfunction "2_2") (pintype "passive"))
    )
    (net (code "55") (name "Net-(SW_PROG-COM_1)") (class "Default")
      (node (ref "SW_PROG") (pin "1") (pinfunction "COM_1_1") (pintype "bidirectional"))
      (node (ref "TO_PICKIT3") (pin "5") (pinfunction "5_5") (pintype "passive"))
    )
    (net (code "56") (name "Net-(SW_PROG-COM_2)") (class "Default")
      (node (ref "SW_PROG") (pin "2") (pinfunction "COM_2_2") (pintype "bidirectional"))
      (node (ref "TO_PICKIT3") (pin "4") (pinfunction "4_4") (pintype "passive"))
    )
    (net (code "57") (name "Net-(SW_PROG-COM_3)") (class "Default")
      (node (ref "SW_PROG") (pin "3") (pinfunction "COM_3_3") (pintype "bidirectional"))
      (node (ref "TO_PICKIT3") (pin "3") (pinfunction "3_3") (pintype "passive"))
    )
    (net (code "58") (name "Net-(SW_PROG-COM_4)") (class "Default")
      (node (ref "SW_PROG") (pin "4") (pinfunction "COM_4_4") (pintype "bidirectional"))
      (node (ref "TO_PICKIT3") (pin "2") (pinfunction "2_2") (pintype "passive"))
    )
    (net (code "59") (name "Net-(SW_PROG-COM_5)") (class "Default")
      (node (ref "SW_PROG") (pin "5") (pinfunction "COM_5_5") (pintype "bidirectional"))
      (node (ref "TO_PICKIT3") (pin "1") (pinfunction "1_1") (pintype "passive"))
    )
    (net (code "60") (name "unconnected-(J1-Pad4)") (class "Default")
      (node (ref "J1") (pin "4") (pinfunction "4_4") (pintype "bidirectional"))
    )
    (net (code "61") (name "unconnected-(J1-PadMP1)") (class "Default")
      (node (ref "J1") (pin "MP1") (pinfunction "MP1_MP1") (pintype "bidirectional"))
    )
    (net (code "62") (name "unconnected-(J1-PadMP2)") (class "Default")
      (node (ref "J1") (pin "MP2") (pinfunction "MP2_MP2") (pintype "bidirectional"))
    )
    (net (code "63") (name "unconnected-(J1-PadMP3)") (class "Default")
      (node (ref "J1") (pin "MP3") (pinfunction "MP3_MP3") (pintype "bidirectional"))
    )
    (net (code "64") (name "unconnected-(J1-PadMP4)") (class "Default")
      (node (ref "J1") (pin "MP4") (pinfunction "MP4_MP4") (pintype "bidirectional"))
    )
  )
)
